# board.net
KiCad netlist of a schematic drawn in EAGLE
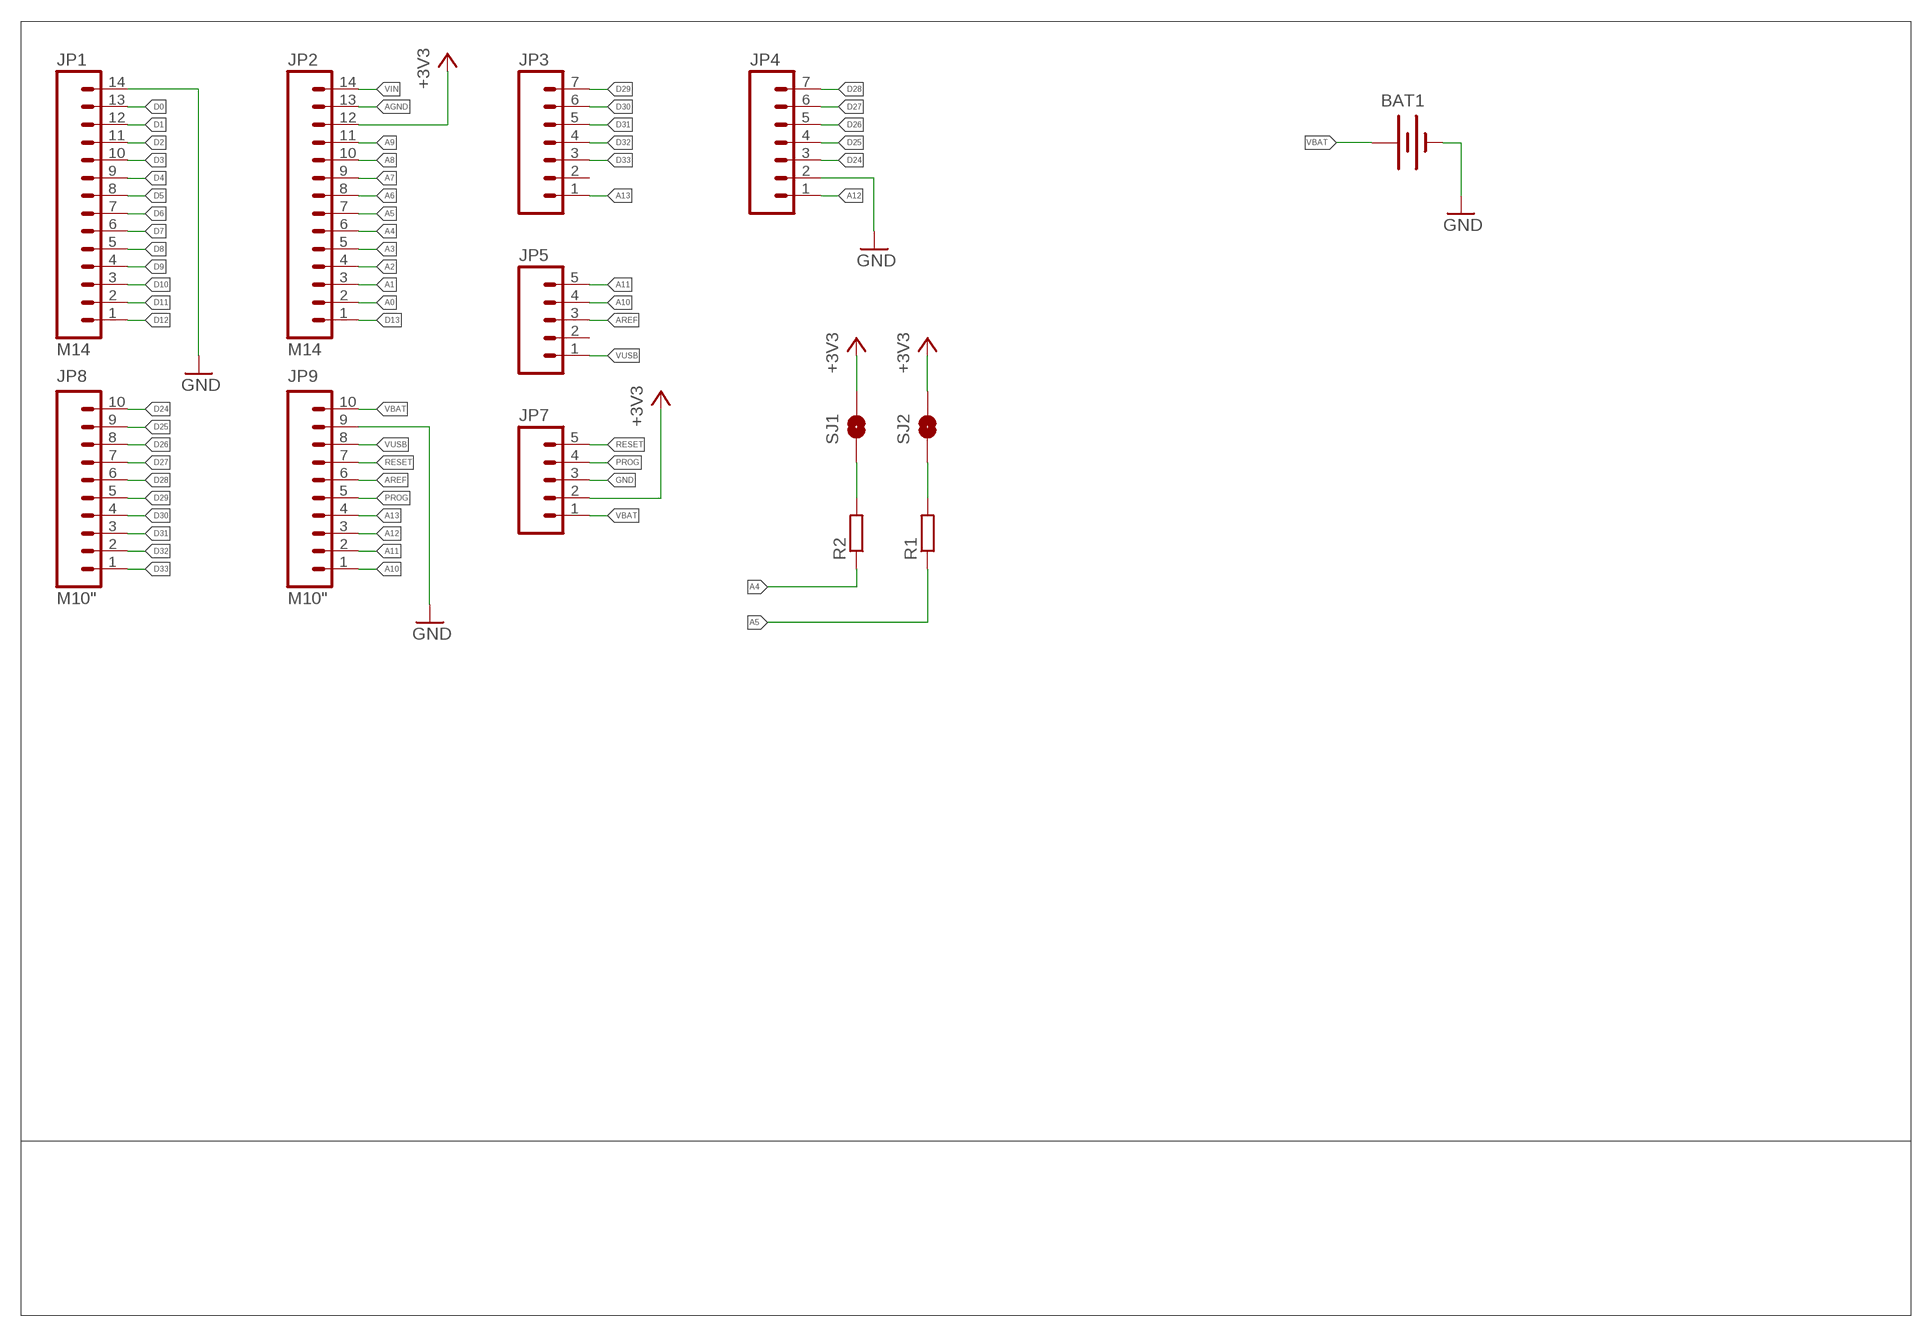
[diagram p0: schematic, sheet 1]

(export (version "E")
  (design (tool "Eeschema 10.0.6"))
  (components
    (comp (ref "BAT1")
      (value "BATTERY12MM")
      (footprint "eagle-import:BATTCON_12MM")
      (libsource (lib "eagle-import") (part "BATTERY12MM"))
    )
    (comp (ref "JP1")
      (value "M14")
      (footprint "eagle-import:1X14")
      (libsource (lib "eagle-import") (part "M14"))
    )
    (comp (ref "JP2")
      (value "M14")
      (footprint "eagle-import:1X14")
      (libsource (lib "eagle-import") (part "M14"))
    )
    (comp (ref "JP3")
      (value "M07")
      (footprint "eagle-import:1X07")
      (libsource (lib "eagle-import") (part "M07"))
    )
    (comp (ref "JP4")
      (value "M07")
      (footprint "eagle-import:1X07")
      (libsource (lib "eagle-import") (part "M07"))
    )
    (comp (ref "JP5")
      (value "M05PTH")
      (footprint "eagle-import:1X05")
      (libsource (lib "eagle-import") (part "M05PTH"))
    )
    (comp (ref "JP7")
      (value "M05PTH")
      (footprint "eagle-import:1X05")
      (libsource (lib "eagle-import") (part "M05PTH"))
    )
    (comp (ref "JP8")
      (value "M10\"")
      (footprint "eagle-import:1X10")
      (libsource (lib "eagle-import") (part "M10{dblquote}"))
    )
    (comp (ref "JP9")
      (value "M10\"")
      (footprint "eagle-import:1X10")
      (libsource (lib "eagle-import") (part "M10{dblquote}"))
    )
    (comp (ref "R1")
      (value "RESISTOR")
      (footprint "eagle-import:R0805")
      (libsource (lib "eagle-import") (part "RESISTOR"))
    )
    (comp (ref "R2")
      (value "RESISTOR")
      (footprint "eagle-import:R0805")
      (libsource (lib "eagle-import") (part "RESISTOR"))
    )
    (comp (ref "SJ1")
      (value "SOLDERJUMPERNO")
      (footprint "eagle-import:SJ_2S-NO")
      (libsource (lib "eagle-import") (part "SOLDERJUMPERNO"))
    )
    (comp (ref "SJ2")
      (value "SOLDERJUMPERNO")
      (footprint "eagle-import:SJ_2S-NO")
      (libsource (lib "eagle-import") (part "SOLDERJUMPERNO"))
    )
  )
  (nets
    (net (code "1") (name "+3V3") (class "Default")
      (node (ref "JP2") (pin "12") (pinfunction "12_12") (pintype "passive"))
      (node (ref "JP7") (pin "2") (pinfunction "2_2") (pintype "passive"))
      (node (ref "SJ1") (pin "2") (pinfunction "2_2") (pintype "passive"))
      (node (ref "SJ2") (pin "2") (pinfunction "2_2") (pintype "passive"))
    )
    (net (code "2") (name "A0") (class "Default")
      (node (ref "JP2") (pin "2") (pinfunction "2_2") (pintype "passive"))
    )
    (net (code "3") (name "A1") (class "Default")
      (node (ref "JP2") (pin "3") (pinfunction "3_3") (pintype "passive"))
    )
    (net (code "4") (name "A2") (class "Default")
      (node (ref "JP2") (pin "4") (pinfunction "4_4") (pintype "passive"))
    )
    (net (code "5") (name "A3") (class "Default")
      (node (ref "JP2") (pin "5") (pinfunction "5_5") (pintype "passive"))
    )
    (net (code "6") (name "A4") (class "Default")
      (node (ref "JP2") (pin "6") (pinfunction "6_6") (pintype "passive"))
      (node (ref "R2") (pin "1") (pinfunction "1_1") (pintype "passive"))
    )
    (net (code "7") (name "A5") (class "Default")
      (node (ref "JP2") (pin "7") (pinfunction "7_7") (pintype "passive"))
      (node (ref "R1") (pin "1") (pinfunction "1_1") (pintype "passive"))
    )
    (net (code "8") (name "A6") (class "Default")
      (node (ref "JP2") (pin "8") (pinfunction "8_8") (pintype "passive"))
    )
    (net (code "9") (name "A7") (class "Default")
      (node (ref "JP2") (pin "9") (pinfunction "9_9") (pintype "passive"))
    )
    (net (code "10") (name "A8") (class "Default")
      (node (ref "JP2") (pin "10") (pinfunction "10_10") (pintype "passive"))
    )
    (net (code "11") (name "A9") (class "Default")
      (node (ref "JP2") (pin "11") (pinfunction "11_11") (pintype "passive"))
    )
    (net (code "12") (name "A10") (class "Default")
      (node (ref "JP5") (pin "4") (pinfunction "4_4") (pintype "passive"))
      (node (ref "JP9") (pin "1") (pinfunction "1_1") (pintype "passive"))
    )
    (net (code "13") (name "A11") (class "Default")
      (node (ref "JP5") (pin "5") (pinfunction "5_5") (pintype "passive"))
      (node (ref "JP9") (pin "2") (pinfunction "2_2") (pintype "passive"))
    )
    (net (code "14") (name "A12") (class "Default")
      (node (ref "JP4") (pin "1") (pinfunction "1_1") (pintype "passive"))
      (node (ref "JP9") (pin "3") (pinfunction "3_3") (pintype "passive"))
    )
    (net (code "15") (name "A13") (class "Default")
      (node (ref "JP3") (pin "1") (pinfunction "1_1") (pintype "passive"))
      (node (ref "JP9") (pin "4") (pinfunction "4_4") (pintype "passive"))
    )
    (net (code "16") (name "AGND") (class "Default")
      (node (ref "JP2") (pin "13") (pinfunction "13_13") (pintype "passive"))
    )
    (net (code "17") (name "AREF") (class "Default")
      (node (ref "JP5") (pin "3") (pinfunction "3_3") (pintype "passive"))
      (node (ref "JP9") (pin "6") (pinfunction "6_6") (pintype "passive"))
    )
    (net (code "18") (name "D0") (class "Default")
      (node (ref "JP1") (pin "13") (pinfunction "13_13") (pintype "passive"))
    )
    (net (code "19") (name "D1") (class "Default")
      (node (ref "JP1") (pin "12") (pinfunction "12_12") (pintype "passive"))
    )
    (net (code "20") (name "D2") (class "Default")
      (node (ref "JP1") (pin "11") (pinfunction "11_11") (pintype "passive"))
    )
    (net (code "21") (name "D3") (class "Default")
      (node (ref "JP1") (pin "10") (pinfunction "10_10") (pintype "passive"))
    )
    (net (code "22") (name "D4") (class "Default")
      (node (ref "JP1") (pin "9") (pinfunction "9_9") (pintype "passive"))
    )
    (net (code "23") (name "D5") (class "Default")
      (node (ref "JP1") (pin "8") (pinfunction "8_8") (pintype "passive"))
    )
    (net (code "24") (name "D6") (class "Default")
      (node (ref "JP1") (pin "7") (pinfunction "7_7") (pintype "passive"))
    )
    (net (code "25") (name "D7") (class "Default")
      (node (ref "JP1") (pin "6") (pinfunction "6_6") (pintype "passive"))
    )
    (net (code "26") (name "D8") (class "Default")
      (node (ref "JP1") (pin "5") (pinfunction "5_5") (pintype "passive"))
    )
    (net (code "27") (name "D9") (class "Default")
      (node (ref "JP1") (pin "4") (pinfunction "4_4") (pintype "passive"))
    )
    (net (code "28") (name "D10") (class "Default")
      (node (ref "JP1") (pin "3") (pinfunction "3_3") (pintype "passive"))
    )
    (net (code "29") (name "D11") (class "Default")
      (node (ref "JP1") (pin "2") (pinfunction "2_2") (pintype "passive"))
    )
    (net (code "30") (name "D12") (class "Default")
      (node (ref "JP1") (pin "1") (pinfunction "1_1") (pintype "passive"))
    )
    (net (code "31") (name "D13") (class "Default")
      (node (ref "JP2") (pin "1") (pinfunction "1_1") (pintype "passive"))
    )
    (net (code "32") (name "D24") (class "Default")
      (node (ref "JP4") (pin "3") (pinfunction "3_3") (pintype "passive"))
      (node (ref "JP8") (pin "10") (pinfunction "10_10") (pintype "passive"))
    )
    (net (code "33") (name "D25") (class "Default")
      (node (ref "JP4") (pin "4") (pinfunction "4_4") (pintype "passive"))
      (node (ref "JP8") (pin "9") (pinfunction "9_9") (pintype "passive"))
    )
    (net (code "34") (name "D26") (class "Default")
      (node (ref "JP4") (pin "5") (pinfunction "5_5") (pintype "passive"))
      (node (ref "JP8") (pin "8") (pinfunction "8_8") (pintype "passive"))
    )
    (net (code "35") (name "D27") (class "Default")
      (node (ref "JP4") (pin "6") (pinfunction "6_6") (pintype "passive"))
      (node (ref "JP8") (pin "7") (pinfunction "7_7") (pintype "passive"))
    )
    (net (code "36") (name "D28") (class "Default")
      (node (ref "JP4") (pin "7") (pinfunction "7_7") (pintype "passive"))
      (node (ref "JP8") (pin "6") (pinfunction "6_6") (pintype "passive"))
    )
    (net (code "37") (name "D29") (class "Default")
      (node (ref "JP3") (pin "7") (pinfunction "7_7") (pintype "passive"))
      (node (ref "JP8") (pin "5") (pinfunction "5_5") (pintype "passive"))
    )
    (net (code "38") (name "D30") (class "Default")
      (node (ref "JP3") (pin "6") (pinfunction "6_6") (pintype "passive"))
      (node (ref "JP8") (pin "4") (pinfunction "4_4") (pintype "passive"))
    )
    (net (code "39") (name "D31") (class "Default")
      (node (ref "JP3") (pin "5") (pinfunction "5_5") (pintype "passive"))
      (node (ref "JP8") (pin "3") (pinfunction "3_3") (pintype "passive"))
    )
    (net (code "40") (name "D32") (class "Default")
      (node (ref "JP3") (pin "4") (pinfunction "4_4") (pintype "passive"))
      (node (ref "JP8") (pin "2") (pinfunction "2_2") (pintype "passive"))
    )
    (net (code "41") (name "D33") (class "Default")
      (node (ref "JP3") (pin "3") (pinfunction "3_3") (pintype "passive"))
      (node (ref "JP8") (pin "1") (pinfunction "1_1") (pintype "passive"))
    )
    (net (code "42") (name "GND") (class "Default")
      (node (ref "BAT1") (pin "GND") (pinfunction "-_GND") (pintype "power_in"))
      (node (ref "JP1") (pin "14") (pinfunction "14_14") (pintype "passive"))
      (node (ref "JP4") (pin "2") (pinfunction "2_2") (pintype "passive"))
      (node (ref "JP7") (pin "3") (pinfunction "3_3") (pintype "passive"))
      (node (ref "JP9") (pin "9") (pinfunction "9_9") (pintype "passive"))
    )
    (net (code "43") (name "Net-(R1-Pad2)") (class "Default")
      (node (ref "R1") (pin "2") (pinfunction "2_2") (pintype "passive"))
      (node (ref "SJ2") (pin "1") (pinfunction "1_1") (pintype "passive"))
    )
    (net (code "44") (name "Net-(R2-Pad2)") (class "Default")
      (node (ref "R2") (pin "2") (pinfunction "2_2") (pintype "passive"))
      (node (ref "SJ1") (pin "1") (pinfunction "1_1") (pintype "passive"))
    )
    (net (code "45") (name "PROG") (class "Default")
      (node (ref "JP7") (pin "4") (pinfunction "4_4") (pintype "passive"))
      (node (ref "JP9") (pin "5") (pinfunction "5_5") (pintype "passive"))
    )
    (net (code "46") (name "RESET") (class "Default")
      (node (ref "JP7") (pin "5") (pinfunction "5_5") (pintype "passive"))
      (node (ref "JP9") (pin "7") (pinfunction "7_7") (pintype "passive"))
    )
    (net (code "47") (name "VBAT") (class "Default")
      (node (ref "BAT1") (pin "PWR@1") (pinfunction "+_PWR@1") (pintype "power_in"))
      (node (ref "JP7") (pin "1") (pinfunction "1_1") (pintype "passive"))
      (node (ref "JP9") (pin "10") (pinfunction "10_10") (pintype "passive"))
    )
    (net (code "48") (name "VIN") (class "Default")
      (node (ref "JP2") (pin "14") (pinfunction "14_14") (pintype "passive"))
    )
    (net (code "49") (name "VUSB") (class "Default")
      (node (ref "JP5") (pin "1") (pinfunction "1_1") (pintype "passive"))
      (node (ref "JP9") (pin "8") (pinfunction "8_8") (pintype "passive"))
    )
    (net (code "50") (name "unconnected-(JP3-Pad2)") (class "Default")
      (node (ref "JP3") (pin "2") (pinfunction "2_2") (pintype "passive"))
    )
    (net (code "51") (name "unconnected-(JP5-Pad2)") (class "Default")
      (node (ref "JP5") (pin "2") (pinfunction "2_2") (pintype "passive"))
    )
  )
)
